# ProDocument_DCATX-ATX24Pin_2023-09-14.net
KiCad netlist of a schematic drawn in EasyEDA Pro
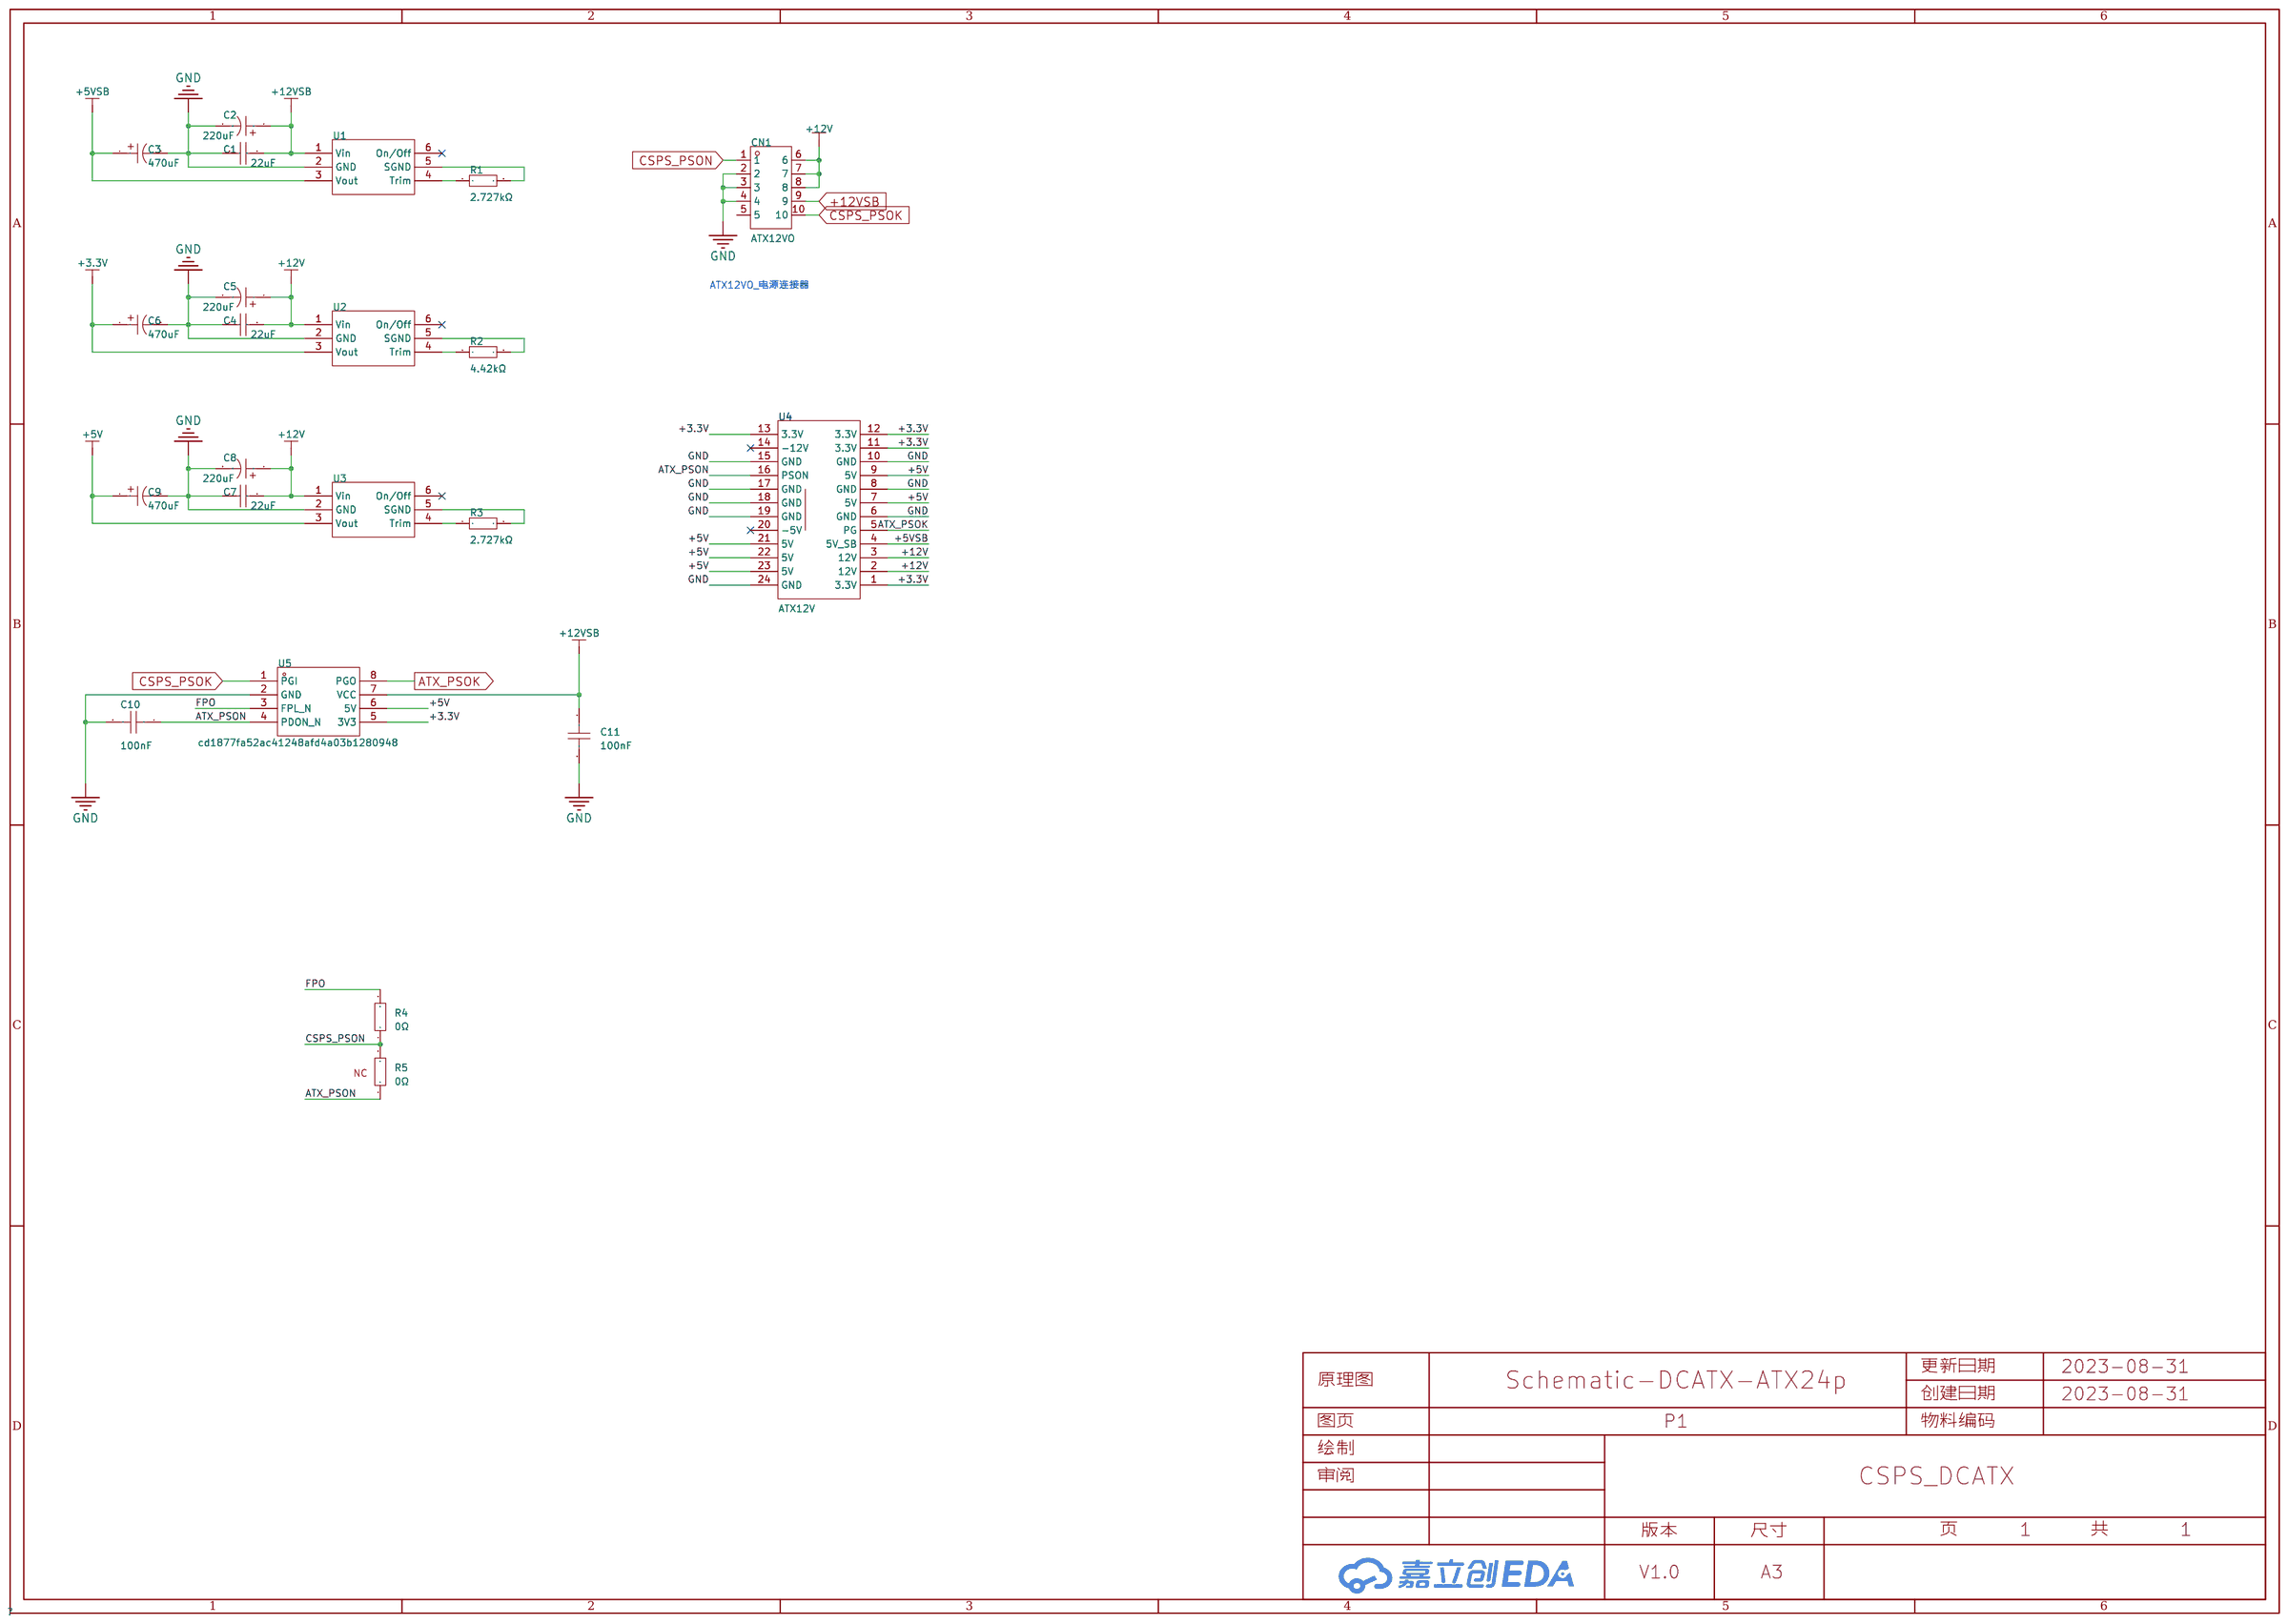
[diagram p0: schematic sheet]

(export (version "E")
  (design (tool "Eeschema 10.0.6"))
  (components
    (comp (ref "C1")
      (value "22uF")
      (footprint "easyedapro:C1206")
      (description "容值:22uF;精度:±10%;额定电压:25V;材质(温度系数):X5R;")
      (fields
        (field (name "Manufacturer Part") "CL31A226KAHNNNE")
        (field (name "Manufacturer") "SAMSUNG(三星)")
      )
      (libsource (lib "easyedapro") (part "CL31A226KAHNNNE"))
    )
    (comp (ref "C2")
      (value "220uF")
      (footprint "easyedapro:CAP-SMD_BD6.3-L6.6-W6.6-FD")
      (description "容值:220uF;精度:±20%;额定电压:16V;纹波电流:110mA@120Hz;等效串联电阻:-;")
      (fields
        (field (name "Manufacturer Part") "RVT220UF16V67RV0015")
        (field (name "Manufacturer") "KNSCHA(科尼盛)")
      )
      (libsource (lib "easyedapro") (part "RVT220UF16V67RV0015"))
    )
    (comp (ref "C3")
      (value "470uF")
      (footprint "easyedapro:CAP-SMD_BD8.0-L8.3-W8.3-LS9.0-FD")
      (description "容值:470uF;额定电压:16V;工作寿命:2000hrs@105°C;")
      (fields
        (field (name "Manufacturer Part") "RVT470UF16V67RV0031")
        (field (name "Manufacturer") "KNSCHA(科尼盛)")
      )
      (libsource (lib "easyedapro") (part "RVT470UF16V67RV0031"))
    )
    (comp (ref "C4")
      (value "22uF")
      (footprint "easyedapro:C1206")
      (description "容值:22uF;精度:±10%;额定电压:25V;材质(温度系数):X5R;")
      (fields
        (field (name "Manufacturer Part") "CL31A226KAHNNNE")
        (field (name "Manufacturer") "SAMSUNG(三星)")
      )
      (libsource (lib "easyedapro") (part "CL31A226KAHNNNE"))
    )
    (comp (ref "C5")
      (value "220uF")
      (footprint "easyedapro:CAP-SMD_BD6.3-L6.6-W6.6-FD")
      (description "容值:220uF;精度:±20%;额定电压:16V;纹波电流:110mA@120Hz;等效串联电阻:-;")
      (fields
        (field (name "Manufacturer Part") "RVT220UF16V67RV0015")
        (field (name "Manufacturer") "KNSCHA(科尼盛)")
      )
      (libsource (lib "easyedapro") (part "RVT220UF16V67RV0015"))
    )
    (comp (ref "C6")
      (value "470uF")
      (footprint "easyedapro:CAP-SMD_BD8.0-L8.3-W8.3-LS9.0-FD")
      (description "容值:470uF;额定电压:16V;工作寿命:2000hrs@105°C;")
      (fields
        (field (name "Manufacturer Part") "RVT470UF16V67RV0031")
        (field (name "Manufacturer") "KNSCHA(科尼盛)")
      )
      (libsource (lib "easyedapro") (part "RVT470UF16V67RV0031"))
    )
    (comp (ref "C7")
      (value "22uF")
      (footprint "easyedapro:C1206")
      (description "容值:22uF;精度:±10%;额定电压:25V;材质(温度系数):X5R;")
      (fields
        (field (name "Manufacturer Part") "CL31A226KAHNNNE")
        (field (name "Manufacturer") "SAMSUNG(三星)")
      )
      (libsource (lib "easyedapro") (part "CL31A226KAHNNNE"))
    )
    (comp (ref "C8")
      (value "220uF")
      (footprint "easyedapro:CAP-SMD_BD6.3-L6.6-W6.6-FD")
      (description "容值:220uF;精度:±20%;额定电压:16V;纹波电流:110mA@120Hz;等效串联电阻:-;")
      (fields
        (field (name "Manufacturer Part") "RVT220UF16V67RV0015")
        (field (name "Manufacturer") "KNSCHA(科尼盛)")
      )
      (libsource (lib "easyedapro") (part "RVT220UF16V67RV0015"))
    )
    (comp (ref "C9")
      (value "470uF")
      (footprint "easyedapro:CAP-SMD_BD8.0-L8.3-W8.3-LS9.0-FD")
      (description "容值:470uF;额定电压:16V;工作寿命:2000hrs@105°C;")
      (fields
        (field (name "Manufacturer Part") "RVT470UF16V67RV0031")
        (field (name "Manufacturer") "KNSCHA(科尼盛)")
      )
      (libsource (lib "easyedapro") (part "RVT470UF16V67RV0031"))
    )
    (comp (ref "C10")
      (value "100nF")
      (footprint "easyedapro:C0603")
      (libsource (lib "easyedapro") (part "CapAcitance"))
    )
    (comp (ref "C11")
      (value "100nF")
      (footprint "easyedapro:C0603")
      (libsource (lib "easyedapro") (part "CapAcitance"))
    )
    (comp (ref "CN1")
      (value "ATX12VO")
      (footprint "easyedapro:CONN-TH_XKB_X9357WR-2X05S-N2SN")
      (fields
        (field (name "Manufacturer Part") "X9357WR-2x05S-N2SN")
        (field (name "Manufacturer") "XKB Connectivity(中国星坤)")
      )
      (libsource (lib "easyedapro") (part "X9357WR-2X05S-N2SN"))
    )
    (comp (ref "R1")
      (value "2.727kΩ")
      (footprint "easyedapro:R0603")
      (description "电阻类型:厚膜电阻;阻值:4.42kΩ;精度:±1%;功率:100mW;")
      (fields
        (field (name "Manufacturer Part") "0603WAF4421T5E")
        (field (name "Manufacturer") "UNI-ROYAL(厚声)")
      )
      (libsource (lib "easyedapro") (part "0603WAF4421T5E"))
    )
    (comp (ref "R2")
      (value "4.42kΩ")
      (footprint "easyedapro:R0603")
      (description "电阻类型:厚膜电阻;阻值:4.42kΩ;精度:±1%;功率:100mW;")
      (fields
        (field (name "Manufacturer Part") "0603WAF4421T5E")
        (field (name "Manufacturer") "UNI-ROYAL(厚声)")
      )
      (libsource (lib "easyedapro") (part "0603WAF4421T5E"))
    )
    (comp (ref "R3")
      (value "2.727kΩ")
      (footprint "easyedapro:R0603")
      (description "电阻类型:厚膜电阻;阻值:4.42kΩ;精度:±1%;功率:100mW;")
      (fields
        (field (name "Manufacturer Part") "0603WAF4421T5E")
        (field (name "Manufacturer") "UNI-ROYAL(厚声)")
      )
      (libsource (lib "easyedapro") (part "0603WAF4421T5E"))
    )
    (comp (ref "R4")
      (value "0Ω")
      (footprint "easyedapro:R0603")
      (description "电阻类型:厚膜电阻;阻值:0Ω;精度:±1%;功率:100mW;")
      (fields
        (field (name "Manufacturer Part") "0603WAF0000T5E")
        (field (name "Manufacturer") "UNI-ROYAL(厚声)")
      )
      (libsource (lib "easyedapro") (part "0603WAF0000T5E"))
    )
    (comp (ref "R5")
      (value "0Ω")
      (footprint "easyedapro:R0603")
      (description "电阻类型:厚膜电阻;阻值:0Ω;精度:±1%;功率:100mW;")
      (fields
        (field (name "Manufacturer Part") "0603WAF0000T5E")
        (field (name "Manufacturer") "UNI-ROYAL(厚声)")
      )
      (libsource (lib "easyedapro") (part "0603WAF0000T5E"))
    )
    (comp (ref "U1")
      (value "~")
      (footprint "easyedapro:NAK12S20-C")
      (description "华为降压模块")
      (fields (field (name "Manufacturer") "HUAWEI"))
      (libsource (lib "easyedapro") (part "NAK12S20-C"))
    )
    (comp (ref "U2")
      (value "~")
      (footprint "easyedapro:NAK12S20-C")
      (description "华为降压模块")
      (fields (field (name "Manufacturer") "HUAWEI"))
      (libsource (lib "easyedapro") (part "NAK12S20-C"))
    )
    (comp (ref "U3")
      (value "~")
      (footprint "easyedapro:NAK12S20-C")
      (description "华为降压模块")
      (fields (field (name "Manufacturer") "HUAWEI"))
      (libsource (lib "easyedapro") (part "NAK12S20-C"))
    )
    (comp (ref "U4")
      (value "ATX12V")
      (footprint "easyedapro:24pin夹板式")
      (libsource (lib "easyedapro") (part "atx24pin夹板式"))
    )
    (comp (ref "U5")
      (value "cd1877fa52ac41248afd4a03b1280948")
      (footprint "easyedapro:SOP-8_L4.9-W3.9-P1.27-LS6.0-BL")
      (libsource (lib "easyedapro") (part "WT7510"))
    )
  )
  (nets
    (net (code "1") (name "+3.3V") (class "Default")
      (node (ref "C6") (pin "1") (pinfunction "1_1") (pintype "input"))
      (node (ref "U2") (pin "3") (pinfunction "Vout_3") (pintype "input"))
      (node (ref "U4") (pin "1") (pinfunction "3.3V_1") (pintype "input"))
      (node (ref "U4") (pin "11") (pinfunction "3.3V_11") (pintype "input"))
      (node (ref "U4") (pin "12") (pinfunction "3.3V_12") (pintype "input"))
      (node (ref "U4") (pin "13") (pinfunction "3.3V_13") (pintype "input"))
      (node (ref "U5") (pin "5") (pinfunction "3V3_5") (pintype "input"))
    )
    (net (code "2") (name "+5V") (class "Default")
      (node (ref "C9") (pin "1") (pinfunction "1_1") (pintype "input"))
      (node (ref "U3") (pin "3") (pinfunction "Vout_3") (pintype "input"))
      (node (ref "U4") (pin "21") (pinfunction "5V_21") (pintype "input"))
      (node (ref "U4") (pin "22") (pinfunction "5V_22") (pintype "input"))
      (node (ref "U4") (pin "23") (pinfunction "5V_23") (pintype "input"))
      (node (ref "U4") (pin "7") (pinfunction "5V_7") (pintype "input"))
      (node (ref "U4") (pin "9") (pinfunction "5V_9") (pintype "input"))
      (node (ref "U5") (pin "6") (pinfunction "5V_6") (pintype "input"))
    )
    (net (code "3") (name "+5VSB") (class "Default")
      (node (ref "C3") (pin "1") (pinfunction "1_1") (pintype "input"))
      (node (ref "U1") (pin "3") (pinfunction "Vout_3") (pintype "input"))
      (node (ref "U4") (pin "4") (pinfunction "5V_SB_4") (pintype "input"))
    )
    (net (code "4") (name "+12V") (class "Default")
      (node (ref "C4") (pin "2") (pinfunction "2_2") (pintype "input"))
      (node (ref "C5") (pin "1") (pinfunction "1_1") (pintype "input"))
      (node (ref "C7") (pin "2") (pinfunction "2_2") (pintype "input"))
      (node (ref "C8") (pin "1") (pinfunction "1_1") (pintype "input"))
      (node (ref "CN1") (pin "6") (pinfunction "6_6") (pintype "input"))
      (node (ref "CN1") (pin "7") (pinfunction "7_7") (pintype "input"))
      (node (ref "CN1") (pin "8") (pinfunction "8_8") (pintype "input"))
      (node (ref "U2") (pin "1") (pinfunction "Vin_1") (pintype "input"))
      (node (ref "U3") (pin "1") (pinfunction "Vin_1") (pintype "input"))
      (node (ref "U4") (pin "2") (pinfunction "12V_2") (pintype "input"))
      (node (ref "U4") (pin "3") (pinfunction "12V_3") (pintype "input"))
    )
    (net (code "5") (name "+12VSB") (class "Default")
      (node (ref "C1") (pin "2") (pinfunction "2_2") (pintype "input"))
      (node (ref "C11") (pin "1") (pinfunction "1_1") (pintype "input"))
      (node (ref "C2") (pin "1") (pinfunction "1_1") (pintype "input"))
      (node (ref "CN1") (pin "9") (pinfunction "9_9") (pintype "input"))
      (node (ref "U1") (pin "1") (pinfunction "Vin_1") (pintype "input"))
      (node (ref "U5") (pin "7") (pinfunction "VCC_7") (pintype "input"))
    )
    (net (code "6") (name "/ATX_PSON") (class "Default")
      (node (ref "C10") (pin "1") (pinfunction "1_1") (pintype "input"))
      (node (ref "R5") (pin "1") (pinfunction "1_1") (pintype "input"))
      (node (ref "U4") (pin "16") (pinfunction "PSON_16") (pintype "input"))
      (node (ref "U5") (pin "4") (pinfunction "PDON_N_4") (pintype "input"))
    )
    (net (code "7") (name "/FPO") (class "Default")
      (node (ref "R4") (pin "2") (pinfunction "2_2") (pintype "input"))
      (node (ref "U5") (pin "3") (pinfunction "FPL_N_3") (pintype "input"))
    )
    (net (code "8") (name "ATX_PSOK") (class "Default")
      (node (ref "U4") (pin "5") (pinfunction "PG_5") (pintype "input"))
      (node (ref "U5") (pin "8") (pinfunction "PGO_8") (pintype "input"))
    )
    (net (code "9") (name "CSPS_PSOK") (class "Default")
      (node (ref "CN1") (pin "10") (pinfunction "10_10") (pintype "input"))
      (node (ref "U5") (pin "1") (pinfunction "PGI_1") (pintype "input"))
    )
    (net (code "10") (name "CSPS_PSON") (class "Default")
      (node (ref "CN1") (pin "1") (pinfunction "1_1") (pintype "input"))
      (node (ref "R4") (pin "1") (pinfunction "1_1") (pintype "input"))
      (node (ref "R5") (pin "2") (pinfunction "2_2") (pintype "input"))
    )
    (net (code "11") (name "GND") (class "Default")
      (node (ref "C1") (pin "1") (pinfunction "1_1") (pintype "input"))
      (node (ref "C10") (pin "2") (pinfunction "2_2") (pintype "input"))
      (node (ref "C11") (pin "2") (pinfunction "2_2") (pintype "input"))
      (node (ref "C2") (pin "2") (pinfunction "2_2") (pintype "input"))
      (node (ref "C3") (pin "2") (pinfunction "2_2") (pintype "input"))
      (node (ref "C4") (pin "1") (pinfunction "1_1") (pintype "input"))
      (node (ref "C5") (pin "2") (pinfunction "2_2") (pintype "input"))
      (node (ref "C6") (pin "2") (pinfunction "2_2") (pintype "input"))
      (node (ref "C7") (pin "1") (pinfunction "1_1") (pintype "input"))
      (node (ref "C8") (pin "2") (pinfunction "2_2") (pintype "input"))
      (node (ref "C9") (pin "2") (pinfunction "2_2") (pintype "input"))
      (node (ref "CN1") (pin "2") (pinfunction "2_2") (pintype "input"))
      (node (ref "CN1") (pin "3") (pinfunction "3_3") (pintype "input"))
      (node (ref "CN1") (pin "4") (pinfunction "4_4") (pintype "input"))
      (node (ref "U1") (pin "2") (pinfunction "GND_2") (pintype "input"))
      (node (ref "U2") (pin "2") (pinfunction "GND_2") (pintype "input"))
      (node (ref "U3") (pin "2") (pinfunction "GND_2") (pintype "input"))
      (node (ref "U4") (pin "10") (pinfunction "GND_10") (pintype "input"))
      (node (ref "U4") (pin "15") (pinfunction "GND_15") (pintype "input"))
      (node (ref "U4") (pin "17") (pinfunction "GND_17") (pintype "input"))
      (node (ref "U4") (pin "18") (pinfunction "GND_18") (pintype "input"))
      (node (ref "U4") (pin "19") (pinfunction "GND_19") (pintype "input"))
      (node (ref "U4") (pin "24") (pinfunction "GND_24") (pintype "input"))
      (node (ref "U4") (pin "6") (pinfunction "GND_6") (pintype "input"))
      (node (ref "U4") (pin "8") (pinfunction "GND_8") (pintype "input"))
      (node (ref "U5") (pin "2") (pinfunction "GND_2") (pintype "input"))
    )
    (net (code "12") (name "Net-(U1-SGND)") (class "Default")
      (node (ref "R1") (pin "2") (pinfunction "2_2") (pintype "input"))
      (node (ref "U1") (pin "5") (pinfunction "SGND_5") (pintype "input"))
    )
    (net (code "13") (name "Net-(U1-Trim)") (class "Default")
      (node (ref "R1") (pin "1") (pinfunction "1_1") (pintype "input"))
      (node (ref "U1") (pin "4") (pinfunction "Trim_4") (pintype "input"))
    )
    (net (code "14") (name "Net-(U2-SGND)") (class "Default")
      (node (ref "R2") (pin "2") (pinfunction "2_2") (pintype "input"))
      (node (ref "U2") (pin "5") (pinfunction "SGND_5") (pintype "input"))
    )
    (net (code "15") (name "Net-(U2-Trim)") (class "Default")
      (node (ref "R2") (pin "1") (pinfunction "1_1") (pintype "input"))
      (node (ref "U2") (pin "4") (pinfunction "Trim_4") (pintype "input"))
    )
    (net (code "16") (name "Net-(U3-SGND)") (class "Default")
      (node (ref "R3") (pin "2") (pinfunction "2_2") (pintype "input"))
      (node (ref "U3") (pin "5") (pinfunction "SGND_5") (pintype "input"))
    )
    (net (code "17") (name "Net-(U3-Trim)") (class "Default")
      (node (ref "R3") (pin "1") (pinfunction "1_1") (pintype "input"))
      (node (ref "U3") (pin "4") (pinfunction "Trim_4") (pintype "input"))
    )
    (net (code "18") (name "unconnected-(CN1-Pad5)") (class "Default")
      (node (ref "CN1") (pin "5") (pinfunction "5_5") (pintype "input"))
    )
    (net (code "19") (name "unconnected-(U1-On{slash}Off-Pad6)") (class "Default")
      (node (ref "U1") (pin "6") (pinfunction "On/Off_6") (pintype "input+no_connect"))
    )
    (net (code "20") (name "unconnected-(U2-On{slash}Off-Pad6)") (class "Default")
      (node (ref "U2") (pin "6") (pinfunction "On/Off_6") (pintype "input+no_connect"))
    )
    (net (code "21") (name "unconnected-(U3-On{slash}Off-Pad6)") (class "Default")
      (node (ref "U3") (pin "6") (pinfunction "On/Off_6") (pintype "input+no_connect"))
    )
    (net (code "22") (name "unconnected-(U4--5V-Pad20)") (class "Default")
      (node (ref "U4") (pin "20") (pinfunction "-5V_20") (pintype "input+no_connect"))
    )
    (net (code "23") (name "unconnected-(U4--12V-Pad14)") (class "Default")
      (node (ref "U4") (pin "14") (pinfunction "-12V_14") (pintype "input+no_connect"))
    )
  )
)
